# Sheet1.net
KiCad netlist of a schematic drawn in Altium Designer
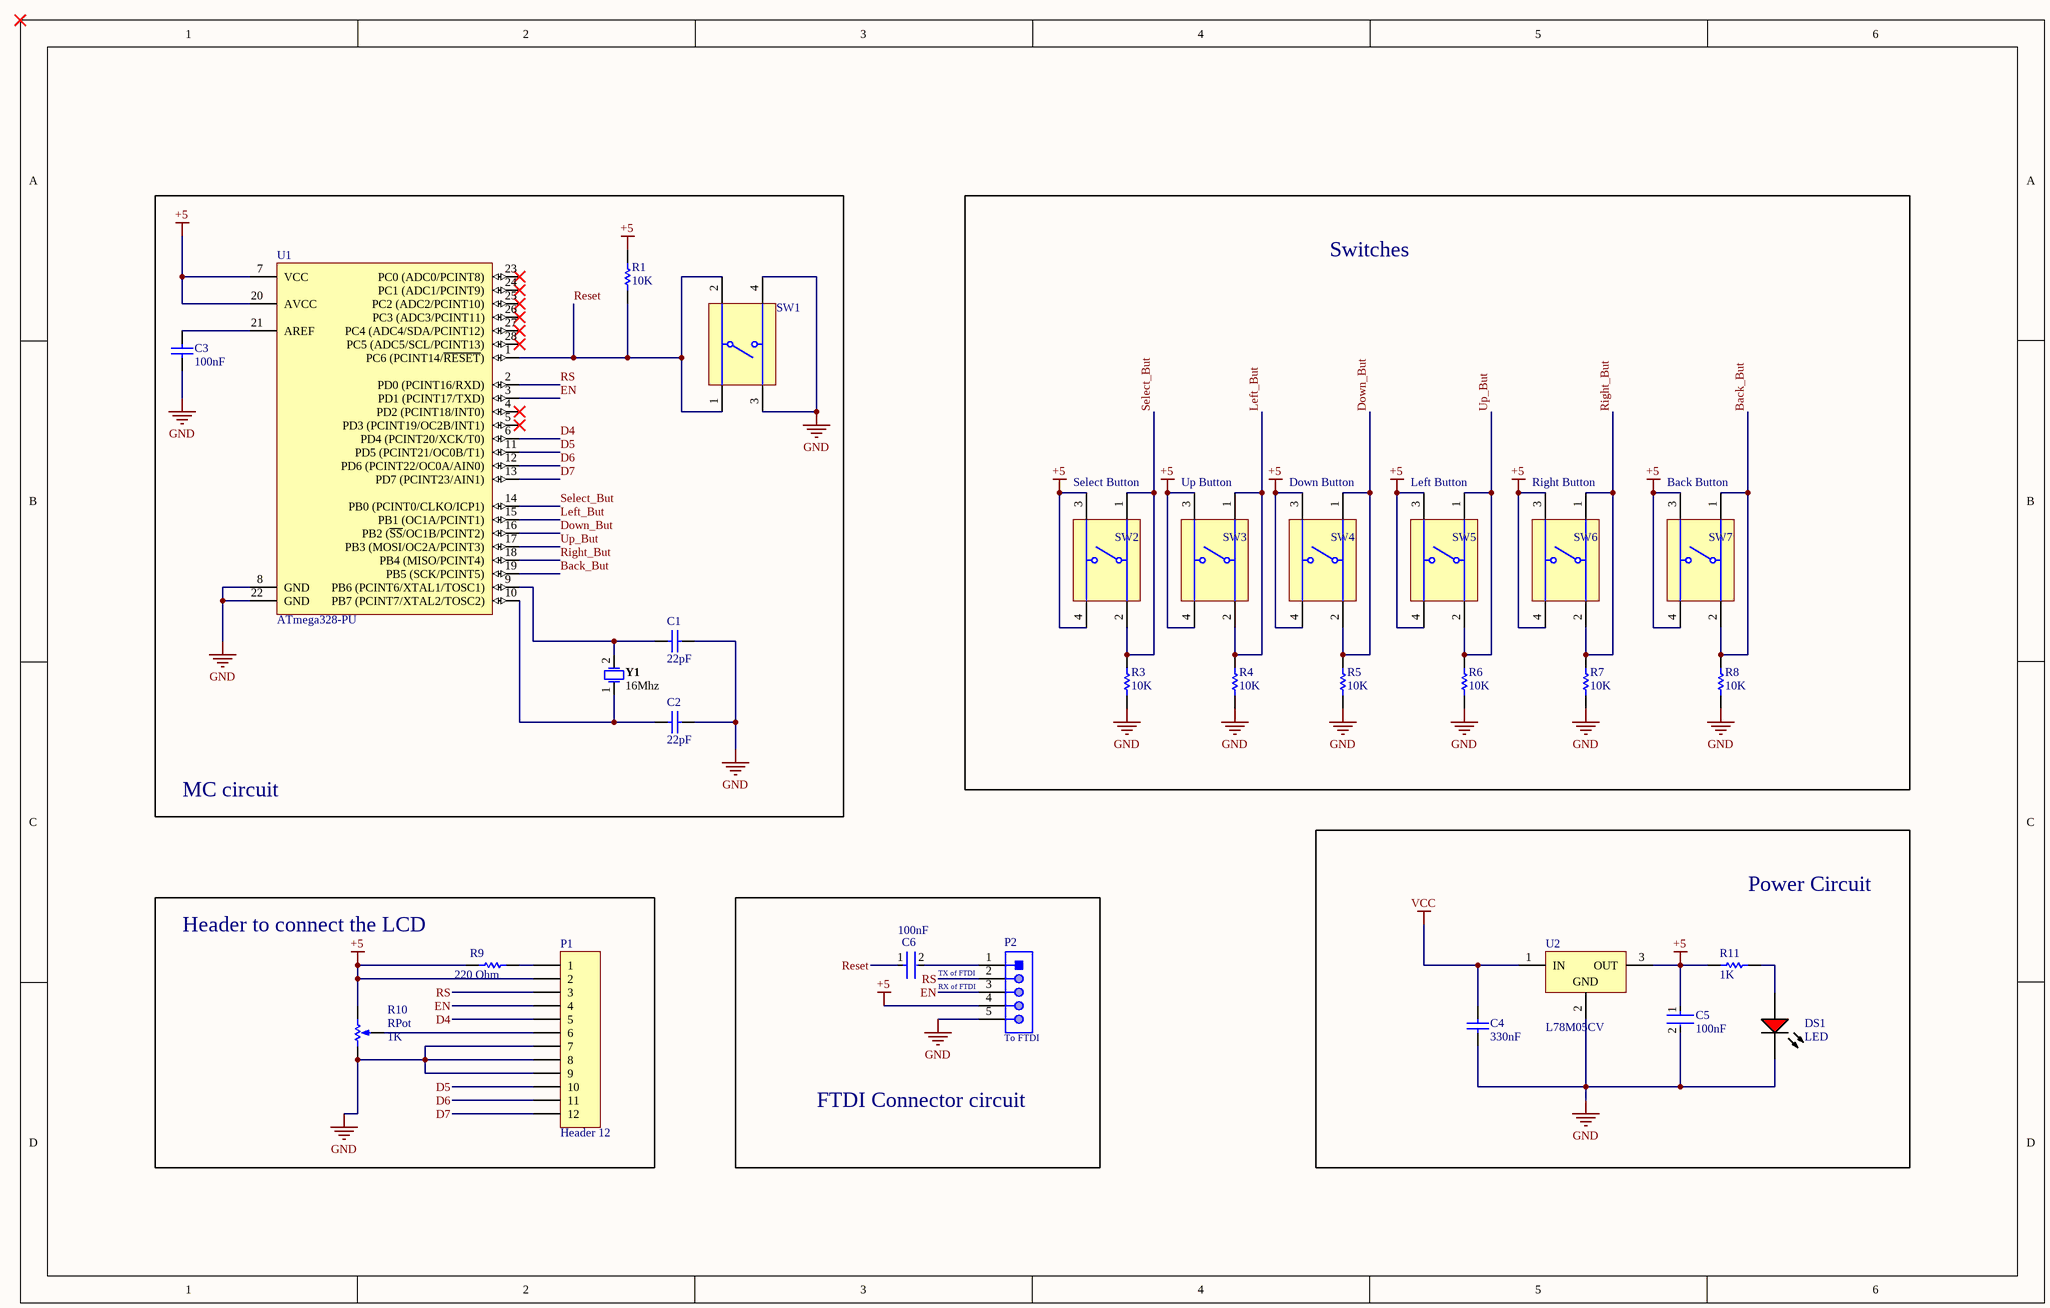
[diagram p0: Sheet1.SchDoc]

(export (version "E")
  (design (tool "Eeschema 10.0.6"))
  (components
    (comp (ref "C1")
      (value "22pF")
      (footprint "RAD-0.3")
      (description "Capacitor")
      (fields (field (name "PUBLISHER") "Altium Limited"))
      (libsource (lib "Miscellaneous Devices") (part "Cap"))
    )
    (comp (ref "C2")
      (value "22pF")
      (footprint "RAD-0.3")
      (description "Capacitor")
      (fields (field (name "PUBLISHER") "Altium Limited"))
      (libsource (lib "Miscellaneous Devices") (part "Cap"))
    )
    (comp (ref "C3")
      (value "100nF")
      (footprint "RAD-0.3")
      (description "Capacitor")
      (fields (field (name "PUBLISHER") "Altium Limited"))
      (libsource (lib "Miscellaneous Devices") (part "Cap"))
    )
    (comp (ref "C4")
      (value "330nF")
      (footprint "CAPC1812(4532)100_L")
      (description "CAP 330nF 50V ±10% 1812 (4532 Metric) Thickness 1mm SMD")
      (fields (field (name "TOLERANCE") "Â±10%"))
      (libsource (lib "Altium Content Vault") (part "CAP"))
    )
    (comp (ref "C5")
      (value "100nF")
      (footprint "FP-CGA3E-0_3-0_1-IPC_A")
      (description "Cap Ceramic 100nF 50V X7R 10% Pad SMD 0603 +125°C Automotive T/R")
      (fields (field (name "TOLERANCE") "10%") (field (name "VOLTAGE") "50V"))
      (libsource (lib "Altium Content Vault") (part "b4654b650e69147ec39a6b967a45e02"))
    )
    (comp (ref "C6")
      (value "100nF")
      (footprint "FP-CGA3E-0_3-0_1-IPC_A")
      (description "Cap Ceramic 100nF 50V X7R 10% Pad SMD 0603 +125°C Automotive T/R")
      (fields (field (name "TOLERANCE") "10%") (field (name "VOLTAGE") "50V"))
      (libsource (lib "Altium Content Vault") (part "b4654b650e69147ec39a6b967a45e02"))
    )
    (comp (ref "DS1")
      (value "LED")
      (footprint "INDPR60-254-520X380X650")
      (description "Radial LED, 12.6 mcd, 20 mA, 2 V, -55 to 100 degC, 2-Pin THD, RoHS, Bulk")
      (fields (field (name "TOLERANCE") "20%"))
      (libsource (lib "Altium Content Vault") (part "LED-RED-AK-2"))
    )
    (comp (ref "P1")
      (value "Header 12")
      (footprint "HDR1X12")
      (description "Header, 12-Pin")
      (fields (field (name "PUBLISHER") "Altium Limited"))
      (libsource (lib "Miscellaneous Connectors") (part "Header 12"))
    )
    (comp (ref "P2")
      (value "To FTDI")
      (footprint "648105131822")
      (description "Male Shrouded Header WR-WTB, SMT, Right Angled, pitch 1.5 mm, 1 x 5 position")
      (fields
        (field (name "MANUFACTURER") "Wurth Elektronik")
        (field (name "PART NUMBER") "648105131822")
        (field (name "PUBLISHER") "WurthElektronik")
      )
      (libsource (lib "Altium Content Vault") (part "WE-CN-1P-M-R5"))
    )
    (comp (ref "R1")
      (value "10K")
      (footprint "AXIAL-0.3")
      (description "Resistor")
      (fields (field (name "PUBLISHER") "Altium Limited"))
      (libsource (lib "Miscellaneous Devices") (part "Res1"))
    )
    (comp (ref "R3")
      (value "10K")
      (footprint "AXIAL-0.3")
      (description "Resistor")
      (fields (field (name "PUBLISHER") "Altium Limited"))
      (libsource (lib "Miscellaneous Devices") (part "Res1"))
    )
    (comp (ref "R4")
      (value "10K")
      (footprint "AXIAL-0.3")
      (description "Resistor")
      (fields (field (name "PUBLISHER") "Altium Limited"))
      (libsource (lib "Miscellaneous Devices") (part "Res1"))
    )
    (comp (ref "R5")
      (value "10K")
      (footprint "AXIAL-0.3")
      (description "Resistor")
      (fields (field (name "PUBLISHER") "Altium Limited"))
      (libsource (lib "Miscellaneous Devices") (part "Res1"))
    )
    (comp (ref "R6")
      (value "10K")
      (footprint "AXIAL-0.3")
      (description "Resistor")
      (fields (field (name "PUBLISHER") "Altium Limited"))
      (libsource (lib "Miscellaneous Devices") (part "Res1"))
    )
    (comp (ref "R7")
      (value "10K")
      (footprint "AXIAL-0.3")
      (description "Resistor")
      (fields (field (name "PUBLISHER") "Altium Limited"))
      (libsource (lib "Miscellaneous Devices") (part "Res1"))
    )
    (comp (ref "R8")
      (value "10K")
      (footprint "AXIAL-0.3")
      (description "Resistor")
      (fields (field (name "PUBLISHER") "Altium Limited"))
      (libsource (lib "Miscellaneous Devices") (part "Res1"))
    )
    (comp (ref "R9")
      (value "220 Ohm")
      (footprint "AXIAL-0.3")
      (description "Resistor")
      (fields (field (name "PUBLISHER") "Altium Limited"))
      (libsource (lib "Miscellaneous Devices") (part "Res1"))
    )
    (comp (ref "R10")
      (value "RPot")
      (footprint "VR5")
      (description "Potentiometer")
      (fields (field (name "ALTIUM_VALUE") "1K") (field (name "PUBLISHER") "Altium Limited"))
      (libsource (lib "Miscellaneous Devices") (part "RPot"))
    )
    (comp (ref "R11")
      (value "1K")
      (footprint "AXIAL-0.3")
      (description "Resistor")
      (fields (field (name "PUBLISHER") "Altium Limited"))
      (libsource (lib "Miscellaneous Devices") (part "Res1"))
    )
    (comp (ref "SW1")
      (value "~")
      (footprint "TECO-FSM4JSMA_V")
      (description "Swicth, SPST, 24 V, -35 to 85 degC, 4-Pin SMD, RoHS, Tape and Reel")
      (fields (field (name "MANUFACTURER") "TE Connectivity"))
      (libsource (lib "") (part "SW-SPST-4_A_1"))
    )
    (comp (ref "SW2")
      (value "Select Button")
      (footprint "TECO-FSM4JSMA_V")
      (description "Swicth, SPST, 24 V, -35 to 85 degC, 4-Pin SMD, RoHS, Tape and Reel")
      (fields (field (name "MANUFACTURER") "TE Connectivity"))
      (libsource (lib "Altium Content Vault") (part "SW-SPST-4_A"))
    )
    (comp (ref "SW3")
      (value "Up Button")
      (footprint "TECO-FSM4JSMA_V")
      (description "Swicth, SPST, 24 V, -35 to 85 degC, 4-Pin SMD, RoHS, Tape and Reel")
      (fields (field (name "MANUFACTURER") "TE Connectivity"))
      (libsource (lib "Altium Content Vault") (part "SW-SPST-4_A"))
    )
    (comp (ref "SW4")
      (value "Down Button")
      (footprint "TECO-FSM4JSMA_V")
      (description "Swicth, SPST, 24 V, -35 to 85 degC, 4-Pin SMD, RoHS, Tape and Reel")
      (fields (field (name "MANUFACTURER") "TE Connectivity"))
      (libsource (lib "Altium Content Vault") (part "SW-SPST-4_A"))
    )
    (comp (ref "SW5")
      (value "Left Button")
      (footprint "TECO-FSM4JSMA_V")
      (description "Swicth, SPST, 24 V, -35 to 85 degC, 4-Pin SMD, RoHS, Tape and Reel")
      (fields (field (name "MANUFACTURER") "TE Connectivity"))
      (libsource (lib "Altium Content Vault") (part "SW-SPST-4_A"))
    )
    (comp (ref "SW6")
      (value "Right Button")
      (footprint "TECO-FSM4JSMA_V")
      (description "Swicth, SPST, 24 V, -35 to 85 degC, 4-Pin SMD, RoHS, Tape and Reel")
      (fields (field (name "MANUFACTURER") "TE Connectivity"))
      (libsource (lib "Altium Content Vault") (part "SW-SPST-4_A"))
    )
    (comp (ref "SW7")
      (value "Back Button")
      (footprint "TECO-FSM4JSMA_V")
      (description "Swicth, SPST, 24 V, -35 to 85 degC, 4-Pin SMD, RoHS, Tape and Reel")
      (fields (field (name "MANUFACTURER") "TE Connectivity"))
      (libsource (lib "Altium Content Vault") (part "SW-SPST-4_A"))
    )
    (comp (ref "U1")
      (value "ATmega328-PU")
      (footprint "28P3")
      (libsource (lib "Altium Content Vault") (part "MC-8B-ATM48-IL28"))
    )
    (comp (ref "U2")
      (value "L78M05CV")
      (footprint "TO220")
      (description "Positive Voltage Regulator, 5V, 3-Pin TO-220")
      (libsource (lib "Altium Content Vault") (part "PM-REG-L4940-SIL3"))
    )
    (comp (ref "Y1")
      (value "16Mhz")
      (footprint "FOX-FOXSLF160-20")
      (description "Resistance Weld Thru-Hole Crystal, 16 MHz, -20 to 70 degC, 2-Pin THD, RoHS, Bulk")
      (fields (field (name "TOLERANCE") "1%"))
      (libsource (lib "Altium Content Vault") (part "XTAL-1-2-2"))
    )
  )
  (nets
    (net (code "1") (name "+5") (class "Default")
      (node (ref "C5") (pin "1") (pinfunction "1_1") (pintype "passive"))
      (node (ref "P1") (pin "2") (pinfunction "2_2") (pintype "passive"))
      (node (ref "P2") (pin "4") (pinfunction "4_4") (pintype "passive"))
      (node (ref "R1") (pin "2") (pinfunction "2_2") (pintype "passive"))
      (node (ref "R10") (pin "2") (pinfunction "BOT_2") (pintype "passive"))
      (node (ref "R11") (pin "1") (pinfunction "1_1") (pintype "passive"))
      (node (ref "R9") (pin "2") (pinfunction "2_2") (pintype "passive"))
      (node (ref "SW2") (pin "3") (pinfunction "3_3") (pintype "passive"))
      (node (ref "SW2") (pin "4") (pinfunction "4_4") (pintype "passive"))
      (node (ref "SW3") (pin "3") (pinfunction "3_3") (pintype "passive"))
      (node (ref "SW3") (pin "4") (pinfunction "4_4") (pintype "passive"))
      (node (ref "SW4") (pin "3") (pinfunction "3_3") (pintype "passive"))
      (node (ref "SW4") (pin "4") (pinfunction "4_4") (pintype "passive"))
      (node (ref "SW5") (pin "3") (pinfunction "3_3") (pintype "passive"))
      (node (ref "SW5") (pin "4") (pinfunction "4_4") (pintype "passive"))
      (node (ref "SW6") (pin "3") (pinfunction "3_3") (pintype "passive"))
      (node (ref "SW6") (pin "4") (pinfunction "4_4") (pintype "passive"))
      (node (ref "SW7") (pin "3") (pinfunction "3_3") (pintype "passive"))
      (node (ref "SW7") (pin "4") (pinfunction "4_4") (pintype "passive"))
      (node (ref "U1") (pin "20") (pinfunction "AVCC_20") (pintype "power_in"))
      (node (ref "U1") (pin "7") (pinfunction "VCC_7") (pintype "power_in"))
      (node (ref "U2") (pin "3") (pinfunction "OUT_3") (pintype "power_in"))
    )
    (net (code "2") (name "/Back_But") (class "Default")
      (node (ref "R8") (pin "2") (pinfunction "2_2") (pintype "passive"))
      (node (ref "SW7") (pin "1") (pinfunction "1_1") (pintype "passive"))
      (node (ref "SW7") (pin "2") (pinfunction "2_2") (pintype "passive"))
      (node (ref "U1") (pin "19") (pinfunction "PB5_(SCK/PCINT5)_19") (pintype "bidirectional"))
    )
    (net (code "3") (name "/D4") (class "Default")
      (node (ref "P1") (pin "5") (pinfunction "5_5") (pintype "passive"))
      (node (ref "U1") (pin "6") (pinfunction "PD4_(PCINT20/XCK/T0)_6") (pintype "bidirectional"))
    )
    (net (code "4") (name "/D5") (class "Default")
      (node (ref "P1") (pin "10") (pinfunction "10_10") (pintype "passive"))
      (node (ref "U1") (pin "11") (pinfunction "PD5_(PCINT21/OC0B/T1)_11") (pintype "bidirectional"))
    )
    (net (code "5") (name "/D6") (class "Default")
      (node (ref "P1") (pin "11") (pinfunction "11_11") (pintype "passive"))
      (node (ref "U1") (pin "12") (pinfunction "PD6_(PCINT22/OC0A/AIN0)_12") (pintype "bidirectional"))
    )
    (net (code "6") (name "/D7") (class "Default")
      (node (ref "P1") (pin "12") (pinfunction "12_12") (pintype "passive"))
      (node (ref "U1") (pin "13") (pinfunction "PD7_(PCINT23/AIN1)_13") (pintype "bidirectional"))
    )
    (net (code "7") (name "/Down_But") (class "Default")
      (node (ref "R5") (pin "2") (pinfunction "2_2") (pintype "passive"))
      (node (ref "SW4") (pin "1") (pinfunction "1_1") (pintype "passive"))
      (node (ref "SW4") (pin "2") (pinfunction "2_2") (pintype "passive"))
      (node (ref "U1") (pin "16") (pinfunction "PB2_(~{SS}/OC1B/PCINT2)_16") (pintype "bidirectional"))
    )
    (net (code "8") (name "/EN") (class "Default")
      (node (ref "P1") (pin "4") (pinfunction "4_4") (pintype "passive"))
      (node (ref "P2") (pin "3") (pinfunction "3_3") (pintype "passive"))
      (node (ref "U1") (pin "3") (pinfunction "PD1_(PCINT17/TXD)_3") (pintype "bidirectional"))
    )
    (net (code "9") (name "/Left_But") (class "Default")
      (node (ref "R4") (pin "2") (pinfunction "2_2") (pintype "passive"))
      (node (ref "SW3") (pin "1") (pinfunction "1_1") (pintype "passive"))
      (node (ref "SW3") (pin "2") (pinfunction "2_2") (pintype "passive"))
      (node (ref "U1") (pin "15") (pinfunction "PB1_(OC1A/PCINT1)_15") (pintype "bidirectional"))
    )
    (net (code "10") (name "/RS") (class "Default")
      (node (ref "P1") (pin "3") (pinfunction "3_3") (pintype "passive"))
      (node (ref "P2") (pin "2") (pinfunction "2_2") (pintype "passive"))
      (node (ref "U1") (pin "2") (pinfunction "PD0_(PCINT16/RXD)_2") (pintype "bidirectional"))
    )
    (net (code "11") (name "/Reset") (class "Default")
      (node (ref "C6") (pin "1") (pinfunction "1_1") (pintype "passive"))
      (node (ref "R1") (pin "1") (pinfunction "1_1") (pintype "passive"))
      (node (ref "SW1") (pin "1") (pinfunction "1_1") (pintype "passive"))
      (node (ref "SW1") (pin "2") (pinfunction "2_2") (pintype "passive"))
      (node (ref "U1") (pin "1") (pinfunction "PC6_(PCINT14/~{RESET})_1") (pintype "bidirectional"))
    )
    (net (code "12") (name "/Right_But") (class "Default")
      (node (ref "R7") (pin "2") (pinfunction "2_2") (pintype "passive"))
      (node (ref "SW6") (pin "1") (pinfunction "1_1") (pintype "passive"))
      (node (ref "SW6") (pin "2") (pinfunction "2_2") (pintype "passive"))
      (node (ref "U1") (pin "18") (pinfunction "PB4_(MISO/PCINT4)_18") (pintype "bidirectional"))
    )
    (net (code "13") (name "/Select_But") (class "Default")
      (node (ref "R3") (pin "2") (pinfunction "2_2") (pintype "passive"))
      (node (ref "SW2") (pin "1") (pinfunction "1_1") (pintype "passive"))
      (node (ref "SW2") (pin "2") (pinfunction "2_2") (pintype "passive"))
      (node (ref "U1") (pin "14") (pinfunction "PB0_(PCINT0/CLKO/ICP1)_14") (pintype "bidirectional"))
    )
    (net (code "14") (name "/Up_But") (class "Default")
      (node (ref "R6") (pin "2") (pinfunction "2_2") (pintype "passive"))
      (node (ref "SW5") (pin "1") (pinfunction "1_1") (pintype "passive"))
      (node (ref "SW5") (pin "2") (pinfunction "2_2") (pintype "passive"))
      (node (ref "U1") (pin "17") (pinfunction "PB3_(MOSI/OC2A/PCINT3)_17") (pintype "bidirectional"))
    )
    (net (code "15") (name "GND") (class "Default")
      (node (ref "C1") (pin "2") (pinfunction "2_2") (pintype "passive"))
      (node (ref "C2") (pin "2") (pinfunction "2_2") (pintype "passive"))
      (node (ref "C3") (pin "1") (pinfunction "1_1") (pintype "passive"))
      (node (ref "C4") (pin "1") (pinfunction "1_1") (pintype "passive"))
      (node (ref "C5") (pin "2") (pinfunction "2_2") (pintype "passive"))
      (node (ref "DS1") (pin "2") (pinfunction "K_2") (pintype "passive"))
      (node (ref "P1") (pin "7") (pinfunction "7_7") (pintype "passive"))
      (node (ref "P1") (pin "8") (pinfunction "8_8") (pintype "passive"))
      (node (ref "P1") (pin "9") (pinfunction "9_9") (pintype "passive"))
      (node (ref "P2") (pin "5") (pinfunction "5_5") (pintype "passive"))
      (node (ref "R10") (pin "1") (pinfunction "TOP_1") (pintype "passive"))
      (node (ref "R3") (pin "1") (pinfunction "1_1") (pintype "passive"))
      (node (ref "R4") (pin "1") (pinfunction "1_1") (pintype "passive"))
      (node (ref "R5") (pin "1") (pinfunction "1_1") (pintype "passive"))
      (node (ref "R6") (pin "1") (pinfunction "1_1") (pintype "passive"))
      (node (ref "R7") (pin "1") (pinfunction "1_1") (pintype "passive"))
      (node (ref "R8") (pin "1") (pinfunction "1_1") (pintype "passive"))
      (node (ref "SW1") (pin "3") (pinfunction "3_3") (pintype "passive"))
      (node (ref "SW1") (pin "4") (pinfunction "4_4") (pintype "passive"))
      (node (ref "U1") (pin "22") (pinfunction "GND_22") (pintype "power_in"))
      (node (ref "U1") (pin "8") (pinfunction "GND_8") (pintype "power_in"))
      (node (ref "U2") (pin "2") (pinfunction "GND_2") (pintype "power_in"))
    )
    (net (code "16") (name "Net-(C6-Pad2)") (class "Default")
      (node (ref "C6") (pin "2") (pinfunction "2_2") (pintype "passive"))
      (node (ref "P2") (pin "1") (pinfunction "1_1") (pintype "passive"))
    )
    (net (code "17") (name "Net-(DS1-A)") (class "Default")
      (node (ref "DS1") (pin "1") (pinfunction "A_1") (pintype "passive"))
      (node (ref "R11") (pin "2") (pinfunction "2_2") (pintype "passive"))
    )
    (net (code "18") (name "Net-(P1-Pad1)") (class "Default")
      (node (ref "P1") (pin "1") (pinfunction "1_1") (pintype "passive"))
      (node (ref "R9") (pin "1") (pinfunction "1_1") (pintype "passive"))
    )
    (net (code "19") (name "Net-(R10-TAP)") (class "Default")
      (node (ref "P1") (pin "6") (pinfunction "6_6") (pintype "passive"))
      (node (ref "R10") (pin "3") (pinfunction "TAP_3") (pintype "passive"))
    )
    (net (code "20") (name "Net-(U1-AREF)") (class "Default")
      (node (ref "C3") (pin "2") (pinfunction "2_2") (pintype "passive"))
      (node (ref "U1") (pin "21") (pinfunction "AREF_21") (pintype "power_in"))
    )
    (net (code "21") (name "Net-(U1-PB6_(PCINT6{slash}XTAL1{slash}TOSC1))") (class "Default")
      (node (ref "C1") (pin "1") (pinfunction "1_1") (pintype "passive"))
      (node (ref "U1") (pin "9") (pinfunction "PB6_(PCINT6/XTAL1/TOSC1)_9") (pintype "bidirectional"))
      (node (ref "Y1") (pin "2") (pinfunction "2_2") (pintype "passive"))
    )
    (net (code "22") (name "Net-(U1-PB7_(PCINT7{slash}XTAL2{slash}TOSC2))") (class "Default")
      (node (ref "C2") (pin "1") (pinfunction "1_1") (pintype "passive"))
      (node (ref "U1") (pin "10") (pinfunction "PB7_(PCINT7/XTAL2/TOSC2)_10") (pintype "bidirectional"))
      (node (ref "Y1") (pin "1") (pinfunction "1_1") (pintype "passive"))
    )
    (net (code "23") (name "VCC") (class "Default")
      (node (ref "C4") (pin "2") (pinfunction "2_2") (pintype "passive"))
      (node (ref "U2") (pin "1") (pinfunction "IN_1") (pintype "power_in"))
    )
    (net (code "24") (name "unconnected-(U1-PC0_(ADC0{slash}PCINT8)-Pad23)") (class "Default")
      (node (ref "U1") (pin "23") (pinfunction "PC0_(ADC0/PCINT8)_23") (pintype "bidirectional+no_connect"))
    )
    (net (code "25") (name "unconnected-(U1-PC1_(ADC1{slash}PCINT9)-Pad24)") (class "Default")
      (node (ref "U1") (pin "24") (pinfunction "PC1_(ADC1/PCINT9)_24") (pintype "bidirectional+no_connect"))
    )
    (net (code "26") (name "unconnected-(U1-PC2_(ADC2{slash}PCINT10)-Pad25)") (class "Default")
      (node (ref "U1") (pin "25") (pinfunction "PC2_(ADC2/PCINT10)_25") (pintype "bidirectional+no_connect"))
    )
    (net (code "27") (name "unconnected-(U1-PC3_(ADC3{slash}PCINT11)-Pad26)") (class "Default")
      (node (ref "U1") (pin "26") (pinfunction "PC3_(ADC3/PCINT11)_26") (pintype "bidirectional+no_connect"))
    )
    (net (code "28") (name "unconnected-(U1-PC4_(ADC4{slash}SDA{slash}PCINT12)-Pad27)") (class "Default")
      (node (ref "U1") (pin "27") (pinfunction "PC4_(ADC4/SDA/PCINT12)_27") (pintype "bidirectional+no_connect"))
    )
    (net (code "29") (name "unconnected-(U1-PC5_(ADC5{slash}SCL{slash}PCINT13)-Pad28)") (class "Default")
      (node (ref "U1") (pin "28") (pinfunction "PC5_(ADC5/SCL/PCINT13)_28") (pintype "bidirectional+no_connect"))
    )
    (net (code "30") (name "unconnected-(U1-PD2_(PCINT18{slash}INT0)-Pad4)") (class "Default")
      (node (ref "U1") (pin "4") (pinfunction "PD2_(PCINT18/INT0)_4") (pintype "bidirectional+no_connect"))
    )
    (net (code "31") (name "unconnected-(U1-PD3_(PCINT19{slash}OC2B{slash}INT1)-Pad5)") (class "Default")
      (node (ref "U1") (pin "5") (pinfunction "PD3_(PCINT19/OC2B/INT1)_5") (pintype "bidirectional+no_connect"))
    )
  )
)
